# CTR_MCU_Signals.net
KiCad netlist of a schematic drawn in Altium Designer
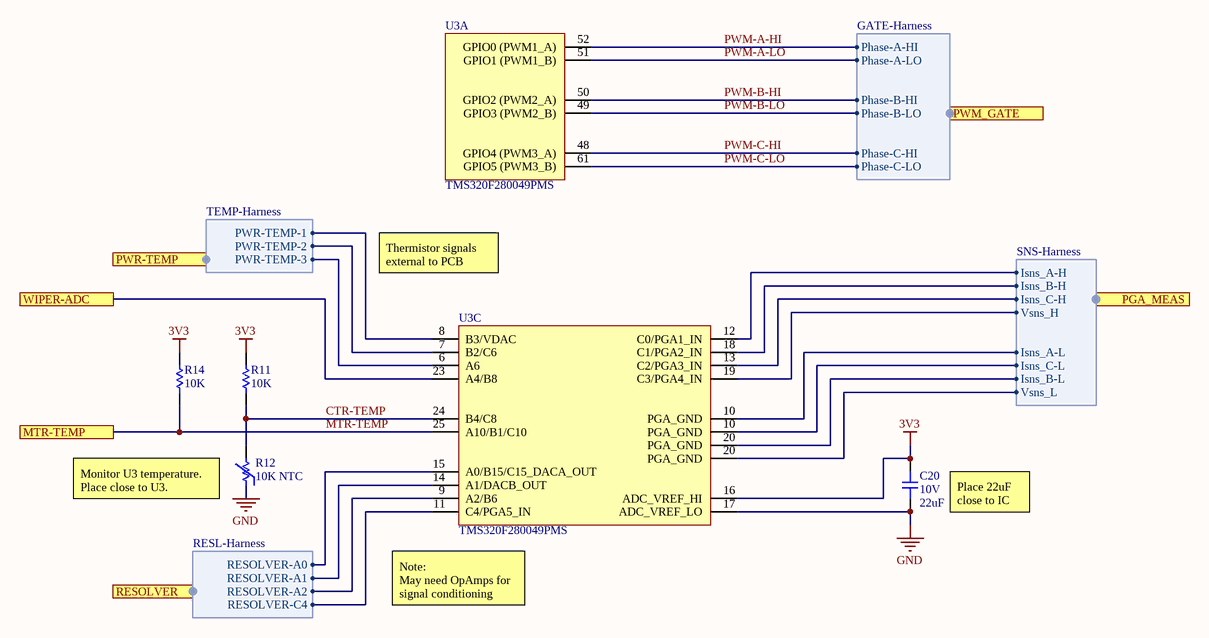
[diagram p0: CTR_MCU_Signals.SchDoc]

(export (version "E")
  (design (tool "Eeschema 10.0.6"))
  (components
    (comp (ref "C20")
      (value "0603-22uF-10V")
      (footprint "CAP-0603")
      (description "CAP CER 22UF 10V X5R 0603")
      (fields
        (field (name "MANUFACTURER") "Murata")
        (field (name "MANUFACTURER PART NUMBER") "GRM187R61A226ME15D")
        (field (name "VOLTAGE RATING") "10V")
        (field (name "CAPACITANCE") "22uF")
      )
      (libsource (lib "InverterSCHLib") (part "0603-22uF-10V"))
    )
    (comp (ref "R11")
      (value "10K")
      (footprint "RES-0603")
      (description "RES SMD 10K OHM 5% 1/10W 0603")
      (fields
        (field (name "MANUFACTURER") "Yageo")
        (field (name "MANUFACTURER PART NUMBER") "RC0603JR-0710KL")
      )
      (libsource (lib "InverterSCHLib") (part "0603-10KR"))
    )
    (comp (ref "R12")
      (value "10K NTC")
      (footprint "RES-0603")
      (description "THERMISTOR NTC 10KOHM 3380K 0603")
      (fields
        (field (name "MANUFACTURER") "Murata")
        (field (name "MANUFACTURER PART NUMBER") "NCP18XH103F03RB")
      )
      (libsource (lib "InverterSCHLib") (part "0603-10K-thermistor"))
    )
    (comp (ref "R14")
      (value "10K")
      (footprint "RES-0603")
      (description "RES SMD 10K OHM 5% 1/10W 0603")
      (fields
        (field (name "MANUFACTURER") "Yageo")
        (field (name "MANUFACTURER PART NUMBER") "RC0603JR-0710KL")
      )
      (libsource (lib "InverterSCHLib") (part "0603-10KR"))
    )
    (comp (ref "U3")
      (value "TMS320F280049PMS")
      (footprint "64QFP")
      (description "IC MCU 32BIT 256KB FLASH 64LQFP")
      (fields
        (field (name "MANUFACTURER") "Texas Instruments")
        (field (name "MANUFACTURER PART NUMBER") "F280049CPMS")
      )
      (libsource (lib "InverterSCHLib") (part "TMS320F280049"))
    )
  )
  (nets
    (net (code "5") (name "/CTR-TEMP") (class "Default")
      (node (ref "R11") (pin "1") (pinfunction "1_1") (pintype "passive"))
      (node (ref "R12") (pin "2") (pinfunction "2_2") (pintype "passive"))
      (node (ref "U3") (pin "24") (pinfunction "B4/C8_24") (pintype "passive"))
    )
    (net (code "6") (name "/Isns_A-H") (class "Default")
      (node (ref "U3") (pin "12") (pinfunction "C0/PGA1_IN_12") (pintype "passive"))
    )
    (net (code "7") (name "/Isns_A-L") (class "Default")
      (node (ref "U3") (pin "10") (pinfunction "PGA_GND_10") (pintype "passive"))
    )
    (net (code "8") (name "/Isns_B-H") (class "Default")
      (node (ref "U3") (pin "18") (pinfunction "C1/PGA2_IN_18") (pintype "passive"))
    )
    (net (code "9") (name "/Isns_B-L") (class "Default")
      (node (ref "U3") (pin "20") (pinfunction "PGA_GND_20") (pintype "passive"))
    )
    (net (code "10") (name "/Isns_C-H") (class "Default")
      (node (ref "U3") (pin "13") (pinfunction "C2/PGA3_IN_13") (pintype "passive"))
    )
    (net (code "11") (name "/Isns_C-L") (class "Default")
      (node (ref "U3") (pin "10") (pinfunction "PGA_GND_10") (pintype "passive"))
    )
    (net (code "12") (name "/MTR-TEMP") (class "Default")
      (node (ref "R14") (pin "1") (pinfunction "1_1") (pintype "passive"))
      (node (ref "U3") (pin "25") (pinfunction "A10/B1/C10_25") (pintype "passive"))
    )
    (net (code "13") (name "/PWM-A-HI") (class "Default")
      (node (ref "U3") (pin "52") (pinfunction "GPIO0_(PWM1_A)_52") (pintype "passive"))
    )
    (net (code "14") (name "/PWM-A-LO") (class "Default")
      (node (ref "U3") (pin "51") (pinfunction "GPIO1_(PWM1_B)_51") (pintype "passive"))
    )
    (net (code "15") (name "/PWM-B-HI") (class "Default")
      (node (ref "U3") (pin "50") (pinfunction "GPIO2_(PWM2_A)_50") (pintype "passive"))
    )
    (net (code "16") (name "/PWM-B-LO") (class "Default")
      (node (ref "U3") (pin "49") (pinfunction "GPIO3_(PWM2_B)_49") (pintype "passive"))
    )
    (net (code "17") (name "/PWM-C-HI") (class "Default")
      (node (ref "U3") (pin "48") (pinfunction "GPIO4_(PWM3_A)_48") (pintype "passive"))
    )
    (net (code "18") (name "/PWM-C-LO") (class "Default")
      (node (ref "U3") (pin "61") (pinfunction "GPIO5_(PWM3_B)_61") (pintype "passive"))
    )
    (net (code "19") (name "/PWR-TEMP-1") (class "Default")
      (node (ref "U3") (pin "8") (pinfunction "B3/VDAC_8") (pintype "passive"))
    )
    (net (code "20") (name "/PWR-TEMP-2") (class "Default")
      (node (ref "U3") (pin "7") (pinfunction "B2/C6_7") (pintype "passive"))
    )
    (net (code "21") (name "/PWR-TEMP-3") (class "Default")
      (node (ref "U3") (pin "6") (pinfunction "A6_6") (pintype "passive"))
    )
    (net (code "22") (name "/RESOLVER-A0") (class "Default")
      (node (ref "U3") (pin "15") (pinfunction "A0/B15/C15_DACA_OUT_15") (pintype "passive"))
    )
    (net (code "23") (name "/RESOLVER-A1") (class "Default")
      (node (ref "U3") (pin "14") (pinfunction "A1/DACB_OUT_14") (pintype "passive"))
    )
    (net (code "24") (name "/RESOLVER-A2") (class "Default")
      (node (ref "U3") (pin "9") (pinfunction "A2/B6_9") (pintype "passive"))
    )
    (net (code "25") (name "/RESOLVER-C4") (class "Default")
      (node (ref "U3") (pin "11") (pinfunction "C4/PGA5_IN_11") (pintype "passive"))
    )
    (net (code "26") (name "/Vsns_H") (class "Default")
      (node (ref "U3") (pin "19") (pinfunction "C3/PGA4_IN_19") (pintype "passive"))
    )
    (net (code "27") (name "/Vsns_L") (class "Default")
      (node (ref "U3") (pin "20") (pinfunction "PGA_GND_20") (pintype "passive"))
    )
    (net (code "28") (name "/WIPER-ADC") (class "Default")
      (node (ref "U3") (pin "23") (pinfunction "A4/B8_23") (pintype "passive"))
    )
    (net (code "33") (name "3V3") (class "Default")
      (node (ref "C20") (pin "2") (pinfunction "2_2") (pintype "passive"))
      (node (ref "R11") (pin "2") (pinfunction "2_2") (pintype "passive"))
      (node (ref "R14") (pin "2") (pinfunction "2_2") (pintype "passive"))
      (node (ref "U3") (pin "16") (pinfunction "ADC_VREF_HI_16") (pintype "passive"))
    )
    (net (code "34") (name "GND") (class "Default")
      (node (ref "C20") (pin "1") (pinfunction "1_1") (pintype "passive"))
      (node (ref "R12") (pin "1") (pinfunction "1_1") (pintype "passive"))
      (node (ref "U3") (pin "17") (pinfunction "ADC_VREF_LO_17") (pintype "passive"))
    )
  )
)
